# RPL_CAN.net
KiCad netlist of a schematic drawn in Altium Designer
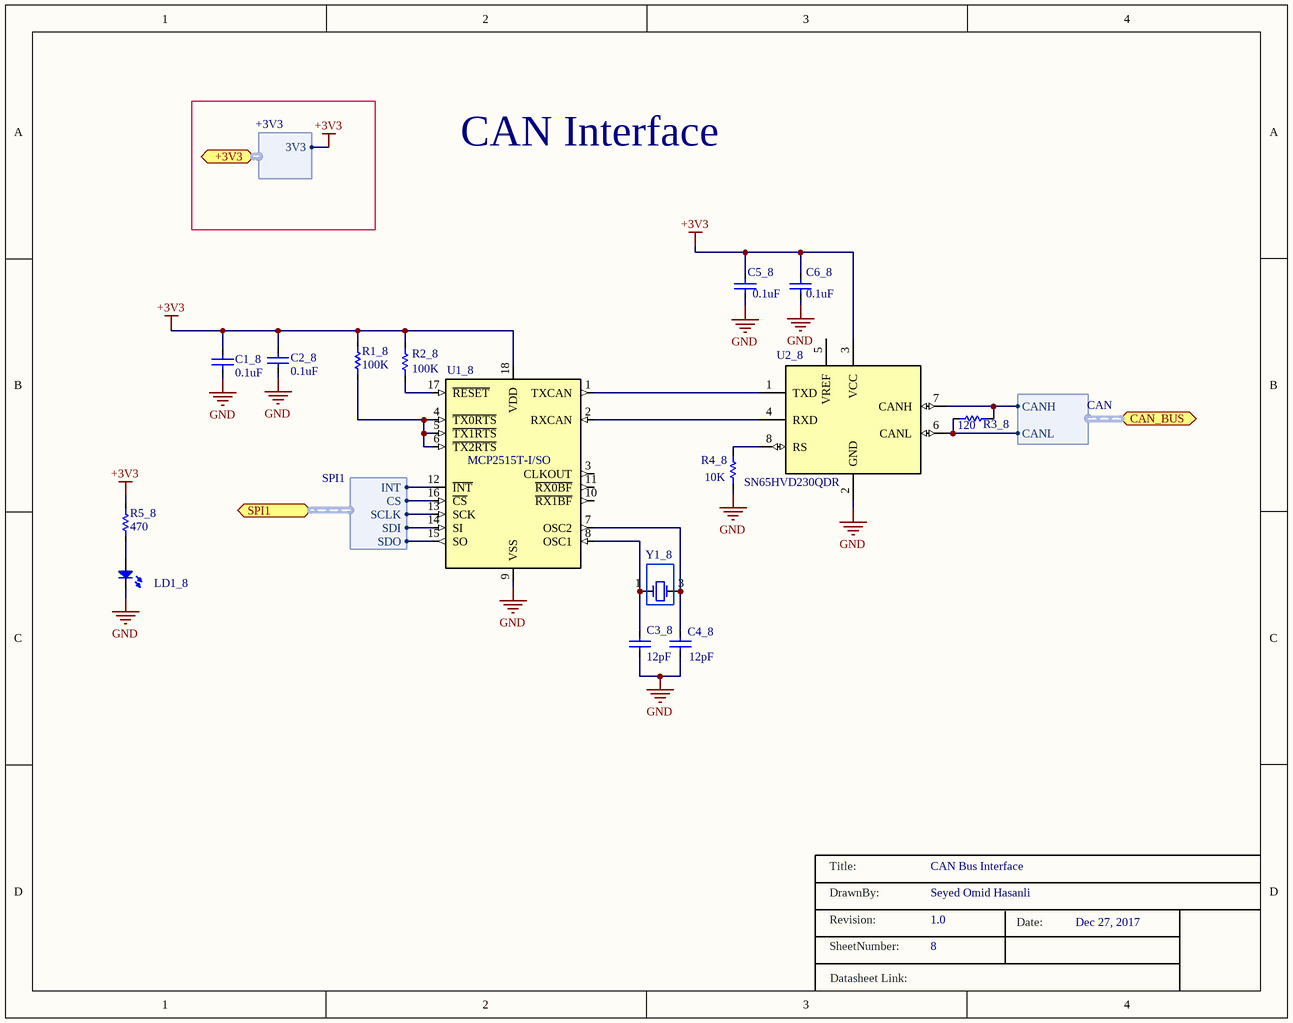
[diagram p0: RPL_CAN.SchDoc]

(export (version "E")
  (design (tool "Eeschema 10.0.6"))
  (components
    (comp (ref "C1_8")
      (value "0.1uF")
      (footprint "C0805C475K9RACAUTO")
      (fields (field (name "Comment") "Cap"))
      (libsource (lib "Generic_Library") (part "Cap"))
    )
    (comp (ref "C2_8")
      (value "0.1uF")
      (footprint "C0805C475K9RACAUTO")
      (fields (field (name "Comment") "Cap"))
      (libsource (lib "Generic_Library") (part "Cap"))
    )
    (comp (ref "C3_8")
      (value "12pF")
      (footprint "C0805C475K9RACAUTO")
      (fields (field (name "Comment") "Cap"))
      (libsource (lib "Generic_Library") (part "Cap"))
    )
    (comp (ref "C4_8")
      (value "12pF")
      (footprint "C0805C475K9RACAUTO")
      (fields (field (name "Comment") "Cap"))
      (libsource (lib "Generic_Library") (part "Cap"))
    )
    (comp (ref "C5_8")
      (value "0.1uF")
      (footprint "C0805C475K9RACAUTO")
      (fields (field (name "Comment") "Cap"))
      (libsource (lib "Generic_Library") (part "Cap"))
    )
    (comp (ref "C6_8")
      (value "0.1uF")
      (footprint "C0805C475K9RACAUTO")
      (fields (field (name "Comment") "Cap"))
      (libsource (lib "Generic_Library") (part "Cap"))
    )
    (comp (ref "LD1_8")
      (value "LED LTST-C190GKT")
      (footprint "LEDM1608X80_LTST-C190GKT(Primary)")
      (description "Green 1.6 x 0.8 x 0.8 mm 130Â° Water Clear 6 mcd 2.1 V SMT LED")
      (fields (field (name "MF") "Lite-On") (field (name "MP") "LTST-C190GKT"))
      (libsource (lib "Generic_Library") (part "LED LTST-C190GKT"))
    )
    (comp (ref "R1_8")
      (value "100K")
      (footprint "SMD Resistors:RES 0805")
      (fields (field (name "Comment") "Res"))
      (libsource (lib "Generic_Library") (part "Res"))
    )
    (comp (ref "R2_8")
      (value "100K")
      (footprint "SMD Resistors:RES 0805")
      (fields (field (name "Comment") "Res"))
      (libsource (lib "Generic_Library") (part "Res"))
    )
    (comp (ref "R3_8")
      (value "120")
      (footprint "SMD Resistors:RES 0805")
      (fields (field (name "Comment") "Res"))
      (libsource (lib "Generic_Library") (part "Res"))
    )
    (comp (ref "R4_8")
      (value "10K")
      (footprint "SMD Resistors:RES 0805")
      (fields (field (name "Comment") "Res"))
      (libsource (lib "Generic_Library") (part "Res"))
    )
    (comp (ref "R5_8")
      (value "470")
      (footprint "SMD Resistors:RES 0805")
      (fields (field (name "Comment") "Res"))
      (libsource (lib "Generic_Library") (part "Res"))
    )
    (comp (ref "U1_8")
      (value "MCP2515T-I/SO")
      (footprint "SOIC18-1.27-11.5X7.5MM")
      (description "MCP2515 Series 5.5 V 1 Mb/s Stand Alone SPI Interface CAN Controller- SOIC-18")
      (fields (field (name "MF") "Microchip"))
      (libsource (lib "Generic_Library") (part "MCP2515T-I/SO (SOIC18)"))
    )
    (comp (ref "U2_8")
      (value "SN65HVD230QDR")
      (footprint "SOIC127P600X175-8N")
      (description "3.3-V CAN Transceiver with Standby Mode 8-SOIC -40 to 125")
      (fields (field (name "MF") "Texas Instruments"))
      (libsource (lib "Generic_Library") (part "SN65HVD230QDR"))
    )
    (comp (ref "Y1_8")
      (value "XTAL_4pin_16MHz_8pF")
      (footprint "OSCSC105P160X120X35-4N")
      (libsource (lib "Generic_Library") (part "XTAL_4pin_16MHz_8pF"))
    )
  )
  (nets
    (net (code "3") (name "+3V3") (class "Default")
      (node (ref "C1_8") (pin "2") (pinfunction "2_2") (pintype "passive"))
      (node (ref "C2_8") (pin "2") (pinfunction "2_2") (pintype "passive"))
      (node (ref "C5_8") (pin "2") (pinfunction "2_2") (pintype "passive"))
      (node (ref "C6_8") (pin "2") (pinfunction "2_2") (pintype "passive"))
      (node (ref "R1_8") (pin "2") (pinfunction "2_2") (pintype "passive"))
      (node (ref "R2_8") (pin "2") (pinfunction "2_2") (pintype "passive"))
      (node (ref "R5_8") (pin "1") (pinfunction "1_1") (pintype "passive"))
      (node (ref "U1_8") (pin "18") (pinfunction "VDD_18") (pintype "power_in"))
      (node (ref "U2_8") (pin "3") (pinfunction "VCC_3") (pintype "power_in"))
    )
    (net (code "4") (name "/CANH") (class "Default")
      (node (ref "R3_8") (pin "1") (pinfunction "1_1") (pintype "passive"))
      (node (ref "U2_8") (pin "7") (pinfunction "CANH_7") (pintype "bidirectional"))
    )
    (net (code "5") (name "/CANL") (class "Default")
      (node (ref "R3_8") (pin "2") (pinfunction "2_2") (pintype "passive"))
      (node (ref "U2_8") (pin "6") (pinfunction "CANL_6") (pintype "bidirectional"))
    )
    (net (code "6") (name "/CS") (class "Default")
      (node (ref "U1_8") (pin "16") (pinfunction "~{CS}_16") (pintype "input"))
    )
    (net (code "7") (name "/INT") (class "Default")
      (node (ref "U1_8") (pin "12") (pinfunction "~{INT}_12") (pintype "passive"))
    )
    (net (code "8") (name "/SCLK") (class "Default")
      (node (ref "U1_8") (pin "13") (pinfunction "SCK_13") (pintype "input"))
    )
    (net (code "9") (name "/SDI") (class "Default")
      (node (ref "U1_8") (pin "14") (pinfunction "SI_14") (pintype "input"))
    )
    (net (code "13") (name "GND") (class "Default")
      (node (ref "C1_8") (pin "1") (pinfunction "1_1") (pintype "passive"))
      (node (ref "C2_8") (pin "1") (pinfunction "1_1") (pintype "passive"))
      (node (ref "C3_8") (pin "2") (pinfunction "2_2") (pintype "passive"))
      (node (ref "C4_8") (pin "2") (pinfunction "2_2") (pintype "passive"))
      (node (ref "C5_8") (pin "1") (pinfunction "1_1") (pintype "passive"))
      (node (ref "C6_8") (pin "1") (pinfunction "1_1") (pintype "passive"))
      (node (ref "LD1_8") (pin "C") (pinfunction "C_C") (pintype "passive"))
      (node (ref "R4_8") (pin "1") (pinfunction "1_1") (pintype "passive"))
      (node (ref "U1_8") (pin "9") (pinfunction "VSS_9") (pintype "power_in"))
      (node (ref "U2_8") (pin "2") (pinfunction "GND_2") (pintype "power_in"))
    )
    (net (code "14") (name "Net-(LD1_8-PadA)") (class "Default")
      (node (ref "LD1_8") (pin "A") (pinfunction "A_A") (pintype "passive"))
      (node (ref "R5_8") (pin "2") (pinfunction "2_2") (pintype "passive"))
    )
    (net (code "15") (name "Net-(U1_8-OSC1)") (class "Default")
      (node (ref "C3_8") (pin "1") (pinfunction "1_1") (pintype "passive"))
      (node (ref "U1_8") (pin "8") (pinfunction "OSC1_8") (pintype "input"))
      (node (ref "Y1_8") (pin "1") (pinfunction "OSC1_1") (pintype "passive"))
    )
    (net (code "16") (name "Net-(U1_8-OSC2)") (class "Default")
      (node (ref "C4_8") (pin "1") (pinfunction "1_1") (pintype "passive"))
      (node (ref "U1_8") (pin "7") (pinfunction "OSC2_7") (pintype "output"))
      (node (ref "Y1_8") (pin "3") (pinfunction "OSC3_3") (pintype "passive"))
    )
    (net (code "17") (name "Net-(U1_8-RXCAN)") (class "Default")
      (node (ref "U1_8") (pin "2") (pinfunction "RXCAN_2") (pintype "input"))
      (node (ref "U2_8") (pin "4") (pinfunction "RXD_4") (pintype "passive"))
    )
    (net (code "18") (name "Net-(U1_8-TXCAN)") (class "Default")
      (node (ref "U1_8") (pin "1") (pinfunction "TXCAN_1") (pintype "output"))
      (node (ref "U2_8") (pin "1") (pinfunction "TXD_1") (pintype "passive"))
    )
    (net (code "19") (name "Net-(U1_8-~{RESET})") (class "Default")
      (node (ref "R2_8") (pin "1") (pinfunction "1_1") (pintype "passive"))
      (node (ref "U1_8") (pin "17") (pinfunction "~{RESET}_17") (pintype "input"))
    )
    (net (code "20") (name "Net-(U1_8-~{TX0RTS})") (class "Default")
      (node (ref "R1_8") (pin "1") (pinfunction "1_1") (pintype "passive"))
      (node (ref "U1_8") (pin "4") (pinfunction "~{TX0RTS}_4") (pintype "input"))
      (node (ref "U1_8") (pin "5") (pinfunction "~{TX1RTS}_5") (pintype "input"))
      (node (ref "U1_8") (pin "6") (pinfunction "~{TX2RTS}_6") (pintype "input"))
    )
    (net (code "21") (name "Net-(U2_8-RS)") (class "Default")
      (node (ref "R4_8") (pin "2") (pinfunction "2_2") (pintype "passive"))
      (node (ref "U2_8") (pin "8") (pinfunction "RS_8") (pintype "bidirectional"))
    )
    (net (code "22") (name "unconnected-(U1_8-CLKOUT-Pad3)") (class "Default")
      (node (ref "U1_8") (pin "3") (pinfunction "CLKOUT_3") (pintype "output"))
    )
    (net (code "23") (name "unconnected-(U1_8-SO-Pad15)") (class "Default")
      (node (ref "U1_8") (pin "15") (pinfunction "SO_15") (pintype "output"))
    )
    (net (code "24") (name "unconnected-(U1_8-~{RX0BF}-Pad11)") (class "Default")
      (node (ref "U1_8") (pin "11") (pinfunction "~{RX0BF}_11") (pintype "output"))
    )
    (net (code "25") (name "unconnected-(U1_8-~{RX1BF}-Pad10)") (class "Default")
      (node (ref "U1_8") (pin "10") (pinfunction "~{RX1BF}_10") (pintype "output"))
    )
    (net (code "26") (name "unconnected-(U2_8-VREF-Pad5)") (class "Default")
      (node (ref "U2_8") (pin "5") (pinfunction "VREF_5") (pintype "passive"))
    )
    (net (code "27") (name "unconnected-(Y1_8-OSC2-Pad2)") (class "Default")
      (node (ref "Y1_8") (pin "2") (pinfunction "OSC2_2") (pintype "passive"))
    )
    (net (code "28") (name "unconnected-(Y1_8-OSC4-Pad4)") (class "Default")
      (node (ref "Y1_8") (pin "4") (pinfunction "OSC4_4") (pintype "passive"))
    )
  )
)
